# EnergyHarvestingBoard.net
KiCad netlist of a schematic drawn in Altium Designer
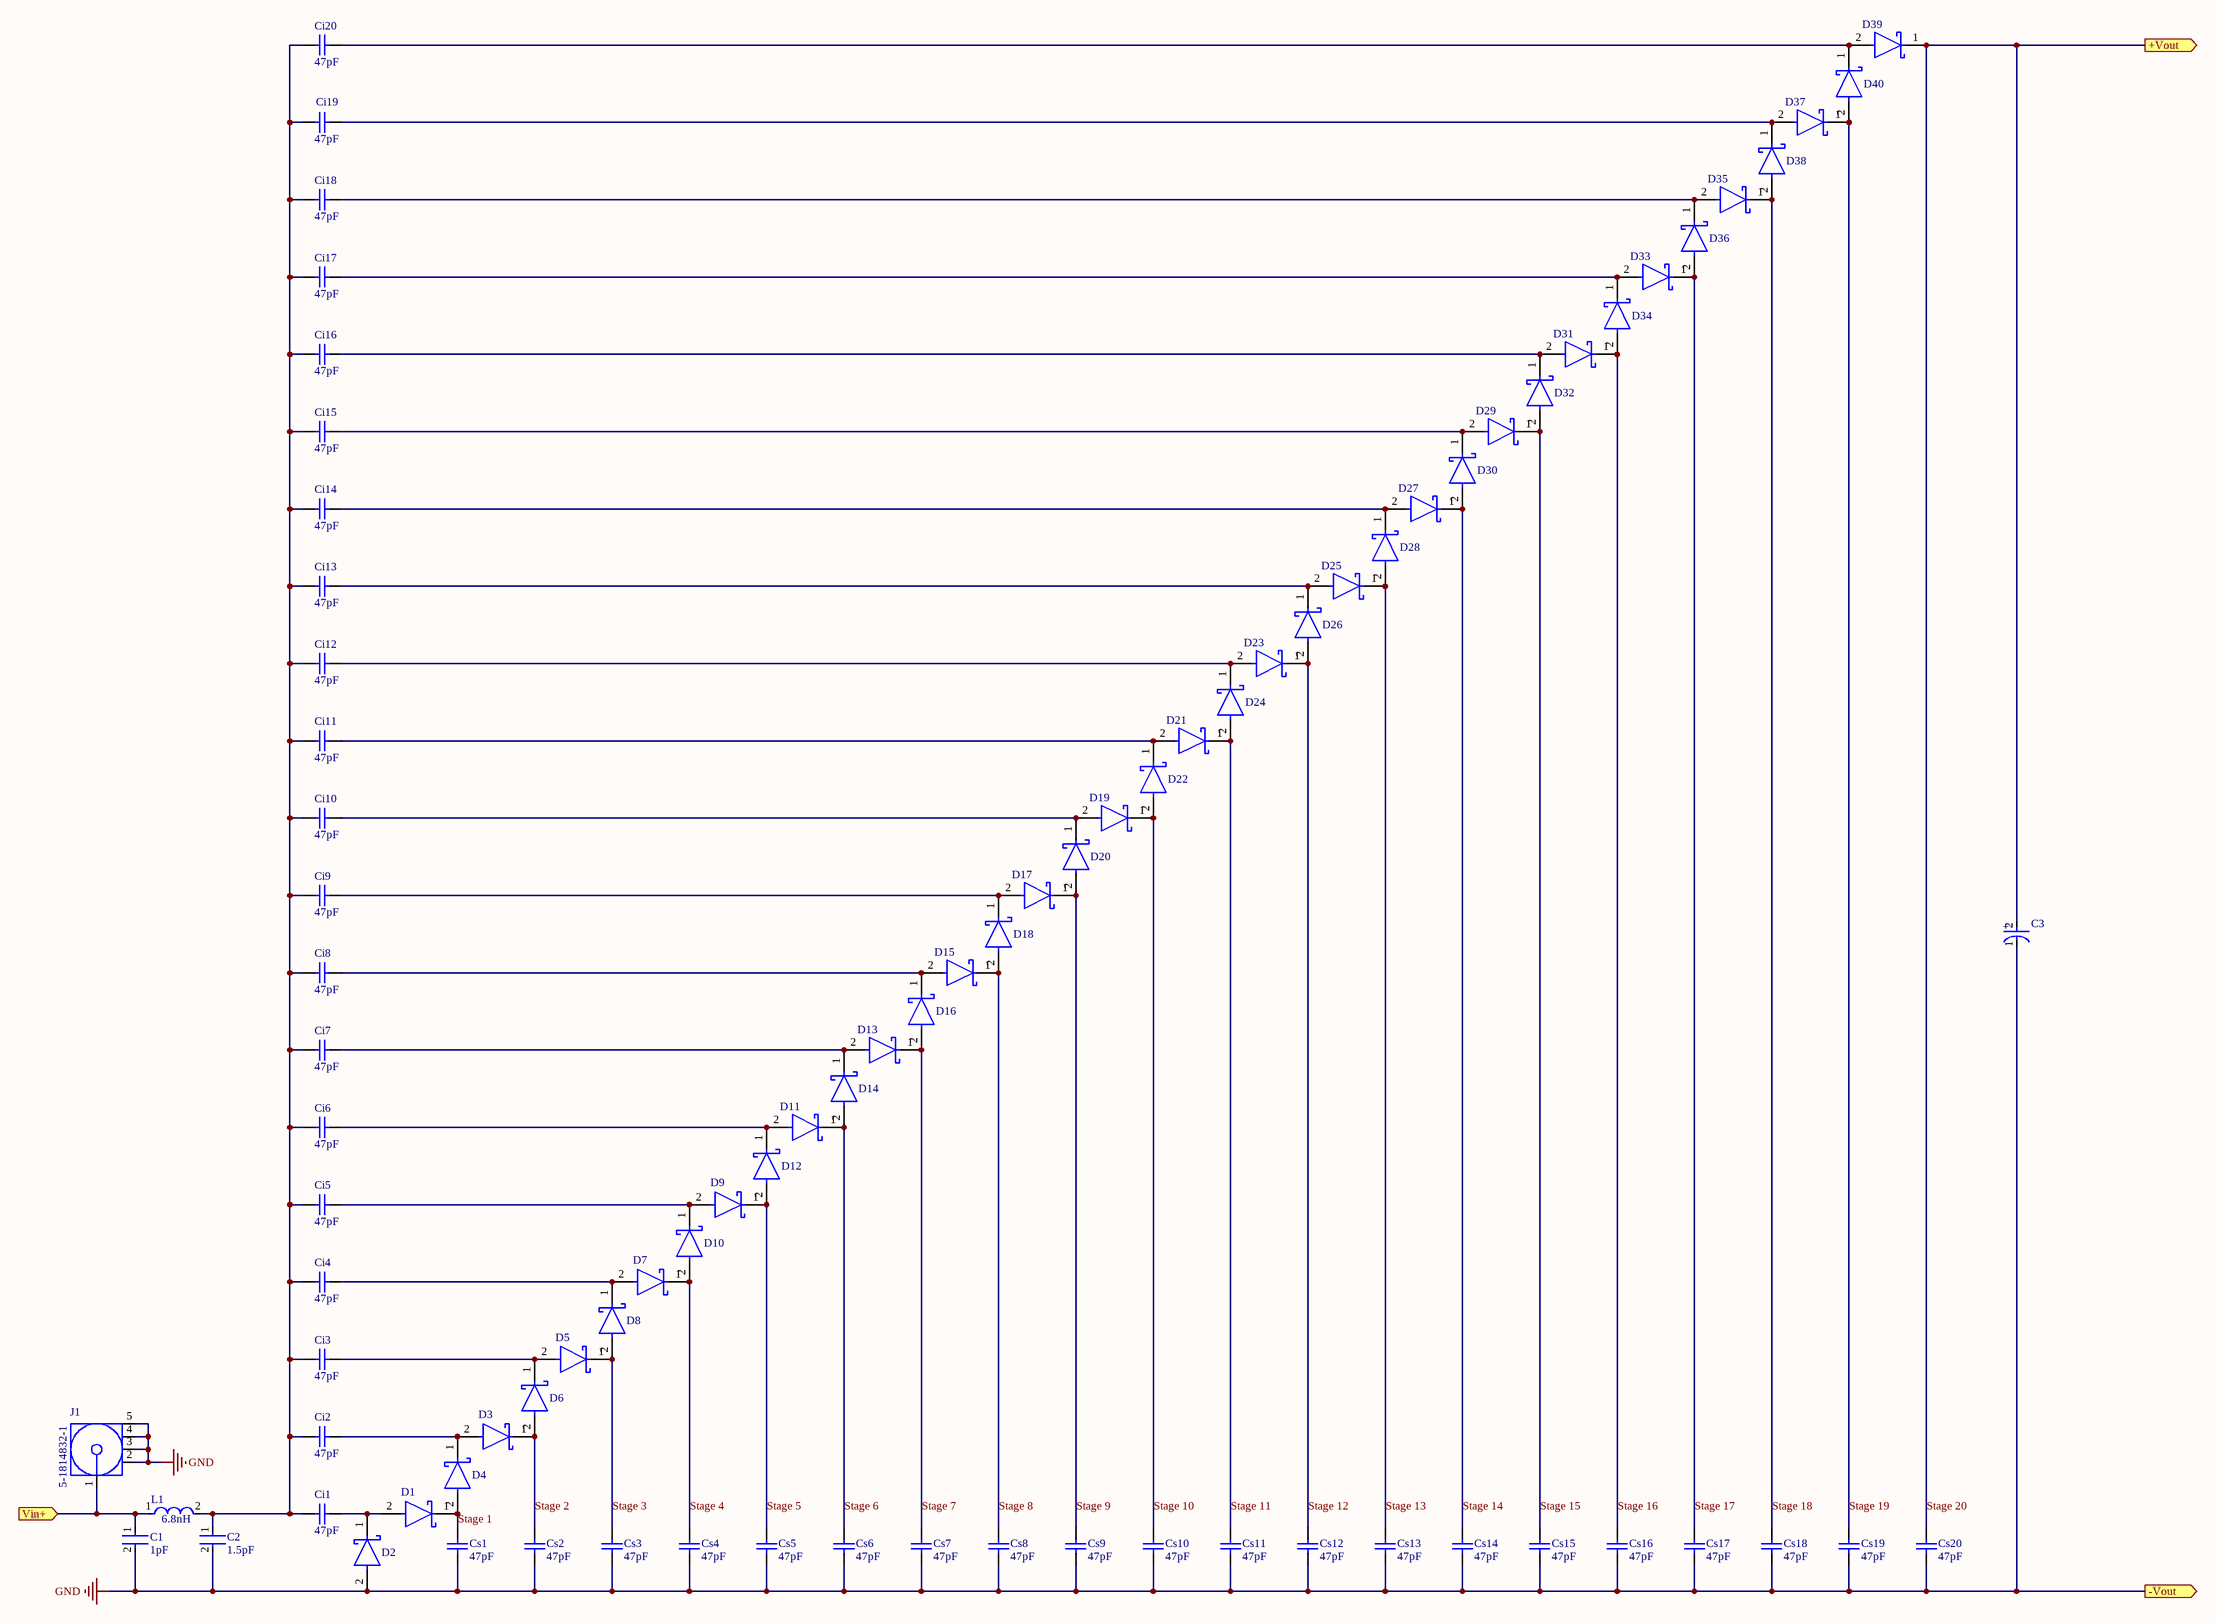
[diagram p0: EnergyHarvestingBoard.SchDoc]

(export (version "E")
  (design (tool "Eeschema 10.0.6"))
  (components
    (comp (ref "C1")
      (value "1pF")
      (footprint "FP-CBR04C-MFG")
      (description "CAP CER 1PF 100V C0G/NP0 0402")
      (fields
        (field (name "MANUFACTURER PART NUMBER") "CBR04C109B1GAC")
        (field (name "MANUFACTURER") "KEMET")
      )
      (libsource (lib "Altium Content Vault") (part "236180d848d6139a670b325ea6854c9"))
    )
    (comp (ref "C2")
      (value "1.5pF")
      (footprint "FP-CBR04C-MFG")
      (description "CBR0402 1.5 pF 30ppm/°C 0.1 pF C0G 100 V")
      (fields (field (name "MANUFACTURER PART NUMBER") "CBR04C159B1GAC"))
      (libsource (lib "Altium Content Vault") (part "236180d848d6139a670b325ea6854c9"))
    )
    (comp (ref "C3")
      (value "EEUEB1JR47S")
      (footprint "FP-RAD-TH-D_5_0_5-L_11_1-MFG")
      (description "Aluminum Electrolytic Capacitors (Radial Lead Type) 0.47uF ±20% 63V")
      (fields (field (name "TOLERANCE") "20%") (field (name "VOLTAGE") "63V"))
      (libsource (lib "Altium Content Vault") (part "a00bbbee19879c290e62620ae7e47b1"))
    )
    (comp (ref "Ci1")
      (value "47pF")
      (footprint "CAPC1005X56X25NL10T15")
      (fields
        (field (name "PART NUMBER") "0402YA470KAT2A")
        (field (name "MANUFACTURER") "AVX Interconnect / Elco")
      )
      (libsource (lib "Altium Content Vault") (part "CAP"))
    )
    (comp (ref "Ci2")
      (value "47pF")
      (footprint "CAPC1005X56X25NL10T15")
      (fields
        (field (name "PART NUMBER") "0402YA470KAT2A")
        (field (name "MANUFACTURER") "AVX Interconnect / Elco")
      )
      (libsource (lib "Altium Content Vault") (part "CAP"))
    )
    (comp (ref "Ci3")
      (value "47pF")
      (footprint "CAPC1005X56X25NL10T15")
      (fields
        (field (name "PART NUMBER") "0402YA470KAT2A")
        (field (name "MANUFACTURER") "AVX Interconnect / Elco")
      )
      (libsource (lib "Altium Content Vault") (part "CAP"))
    )
    (comp (ref "Ci4")
      (value "47pF")
      (footprint "CAPC1005X56X25NL10T15")
      (fields
        (field (name "PART NUMBER") "0402YA470KAT2A")
        (field (name "MANUFACTURER") "AVX Interconnect / Elco")
      )
      (libsource (lib "Altium Content Vault") (part "CAP"))
    )
    (comp (ref "Ci5")
      (value "47pF")
      (footprint "CAPC1005X56X25NL10T15")
      (fields
        (field (name "PART NUMBER") "0402YA470KAT2A")
        (field (name "MANUFACTURER") "AVX Interconnect / Elco")
      )
      (libsource (lib "Altium Content Vault") (part "CAP"))
    )
    (comp (ref "Ci6")
      (value "47pF")
      (footprint "CAPC1005X56X25NL10T15")
      (fields
        (field (name "PART NUMBER") "0402YA470KAT2A")
        (field (name "MANUFACTURER") "AVX Interconnect / Elco")
      )
      (libsource (lib "Altium Content Vault") (part "CAP"))
    )
    (comp (ref "Ci7")
      (value "47pF")
      (footprint "CAPC1005X56X25NL10T15")
      (fields
        (field (name "PART NUMBER") "0402YA470KAT2A")
        (field (name "MANUFACTURER") "AVX Interconnect / Elco")
      )
      (libsource (lib "Altium Content Vault") (part "CAP"))
    )
    (comp (ref "Ci8")
      (value "47pF")
      (footprint "CAPC1005X56X25NL10T15")
      (fields
        (field (name "PART NUMBER") "0402YA470KAT2A")
        (field (name "MANUFACTURER") "AVX Interconnect / Elco")
      )
      (libsource (lib "Altium Content Vault") (part "CAP"))
    )
    (comp (ref "Ci9")
      (value "47pF")
      (footprint "CAPC1005X56X25NL10T15")
      (fields
        (field (name "PART NUMBER") "0402YA470KAT2A")
        (field (name "MANUFACTURER") "AVX Interconnect / Elco")
      )
      (libsource (lib "Altium Content Vault") (part "CAP"))
    )
    (comp (ref "Ci10")
      (value "47pF")
      (footprint "CAPC1005X56X25NL10T15")
      (fields
        (field (name "PART NUMBER") "0402YA470KAT2A")
        (field (name "MANUFACTURER") "AVX Interconnect / Elco")
      )
      (libsource (lib "Altium Content Vault") (part "CAP"))
    )
    (comp (ref "Ci11")
      (value "47pF")
      (footprint "CAPC1005X56X25NL10T15")
      (fields
        (field (name "PART NUMBER") "0402YA470KAT2A")
        (field (name "MANUFACTURER") "AVX Interconnect / Elco")
      )
      (libsource (lib "Altium Content Vault") (part "CAP"))
    )
    (comp (ref "Ci12")
      (value "47pF")
      (footprint "CAPC1005X56X25NL10T15")
      (fields
        (field (name "PART NUMBER") "0402YA470KAT2A")
        (field (name "MANUFACTURER") "AVX Interconnect / Elco")
      )
      (libsource (lib "Altium Content Vault") (part "CAP"))
    )
    (comp (ref "Ci13")
      (value "47pF")
      (footprint "CAPC1005X56X25NL10T15")
      (fields
        (field (name "PART NUMBER") "0402YA470KAT2A")
        (field (name "MANUFACTURER") "AVX Interconnect / Elco")
      )
      (libsource (lib "Altium Content Vault") (part "CAP"))
    )
    (comp (ref "Ci14")
      (value "47pF")
      (footprint "CAPC1005X56X25NL10T15")
      (fields
        (field (name "PART NUMBER") "0402YA470KAT2A")
        (field (name "MANUFACTURER") "AVX Interconnect / Elco")
      )
      (libsource (lib "Altium Content Vault") (part "CAP"))
    )
    (comp (ref "Ci15")
      (value "47pF")
      (footprint "CAPC1005X56X25NL10T15")
      (fields
        (field (name "PART NUMBER") "0402YA470KAT2A")
        (field (name "MANUFACTURER") "AVX Interconnect / Elco")
      )
      (libsource (lib "Altium Content Vault") (part "CAP"))
    )
    (comp (ref "Ci16")
      (value "47pF")
      (footprint "CAPC1005X56X25NL10T15")
      (fields
        (field (name "PART NUMBER") "0402YA470KAT2A")
        (field (name "MANUFACTURER") "AVX Interconnect / Elco")
      )
      (libsource (lib "Altium Content Vault") (part "CAP"))
    )
    (comp (ref "Ci17")
      (value "47pF")
      (footprint "CAPC1005X56X25NL10T15")
      (fields
        (field (name "PART NUMBER") "0402YA470KAT2A")
        (field (name "MANUFACTURER") "AVX Interconnect / Elco")
      )
      (libsource (lib "Altium Content Vault") (part "CAP"))
    )
    (comp (ref "Ci18")
      (value "47pF")
      (footprint "CAPC1005X56X25NL10T15")
      (fields
        (field (name "PART NUMBER") "0402YA470KAT2A")
        (field (name "MANUFACTURER") "AVX Interconnect / Elco")
      )
      (libsource (lib "Altium Content Vault") (part "CAP"))
    )
    (comp (ref "Ci19")
      (value "47pF")
      (footprint "CAPC1005X56X25NL10T15")
      (fields
        (field (name "PART NUMBER") "0402YA470KAT2A")
        (field (name "MANUFACTURER") "AVX Interconnect / Elco")
      )
      (libsource (lib "Altium Content Vault") (part "CAP"))
    )
    (comp (ref "Ci20")
      (value "47pF")
      (footprint "CAPC1005X56X25NL10T15")
      (fields
        (field (name "PART NUMBER") "0402YA470KAT2A")
        (field (name "MANUFACTURER") "AVX Interconnect / Elco")
      )
      (libsource (lib "Altium Content Vault") (part "CAP"))
    )
    (comp (ref "Cs1")
      (value "47pF")
      (footprint "CAPC1005X56X25NL10T15")
      (fields
        (field (name "PART NUMBER") "0402YA470KAT2A")
        (field (name "MANUFACTURER") "AVX Interconnect / Elco")
      )
      (libsource (lib "Altium Content Vault") (part "CAP"))
    )
    (comp (ref "Cs2")
      (value "47pF")
      (footprint "CAPC1005X56X25NL10T15")
      (fields
        (field (name "PART NUMBER") "0402YA470KAT2A")
        (field (name "MANUFACTURER") "AVX Interconnect / Elco")
      )
      (libsource (lib "Altium Content Vault") (part "CAP"))
    )
    (comp (ref "Cs3")
      (value "47pF")
      (footprint "CAPC1005X56X25NL10T15")
      (fields
        (field (name "PART NUMBER") "0402YA470KAT2A")
        (field (name "MANUFACTURER") "AVX Interconnect / Elco")
      )
      (libsource (lib "Altium Content Vault") (part "CAP"))
    )
    (comp (ref "Cs4")
      (value "47pF")
      (footprint "CAPC1005X56X25NL10T15")
      (fields
        (field (name "PART NUMBER") "0402YA470KAT2A")
        (field (name "MANUFACTURER") "AVX Interconnect / Elco")
      )
      (libsource (lib "Altium Content Vault") (part "CAP"))
    )
    (comp (ref "Cs5")
      (value "47pF")
      (footprint "CAPC1005X56X25NL10T15")
      (fields
        (field (name "PART NUMBER") "0402YA470KAT2A")
        (field (name "MANUFACTURER") "AVX Interconnect / Elco")
      )
      (libsource (lib "Altium Content Vault") (part "CAP"))
    )
    (comp (ref "Cs6")
      (value "47pF")
      (footprint "CAPC1005X56X25NL10T15")
      (fields
        (field (name "PART NUMBER") "0402YA470KAT2A")
        (field (name "MANUFACTURER") "AVX Interconnect / Elco")
      )
      (libsource (lib "Altium Content Vault") (part "CAP"))
    )
    (comp (ref "Cs7")
      (value "47pF")
      (footprint "CAPC1005X56X25NL10T15")
      (fields
        (field (name "PART NUMBER") "0402YA470KAT2A")
        (field (name "MANUFACTURER") "AVX Interconnect / Elco")
      )
      (libsource (lib "Altium Content Vault") (part "CAP"))
    )
    (comp (ref "Cs8")
      (value "47pF")
      (footprint "CAPC1005X56X25NL10T15")
      (fields
        (field (name "PART NUMBER") "0402YA470KAT2A")
        (field (name "MANUFACTURER") "AVX Interconnect / Elco")
      )
      (libsource (lib "Altium Content Vault") (part "CAP"))
    )
    (comp (ref "Cs9")
      (value "47pF")
      (footprint "CAPC1005X56X25NL10T15")
      (fields
        (field (name "PART NUMBER") "0402YA470KAT2A")
        (field (name "MANUFACTURER") "AVX Interconnect / Elco")
      )
      (libsource (lib "Altium Content Vault") (part "CAP"))
    )
    (comp (ref "Cs10")
      (value "47pF")
      (footprint "CAPC1005X56X25NL10T15")
      (fields
        (field (name "PART NUMBER") "0402YA470KAT2A")
        (field (name "MANUFACTURER") "AVX Interconnect / Elco")
      )
      (libsource (lib "Altium Content Vault") (part "CAP"))
    )
    (comp (ref "Cs11")
      (value "47pF")
      (footprint "CAPC1005X56X25NL10T15")
      (fields
        (field (name "PART NUMBER") "0402YA470KAT2A")
        (field (name "MANUFACTURER") "AVX Interconnect / Elco")
      )
      (libsource (lib "Altium Content Vault") (part "CAP"))
    )
    (comp (ref "Cs12")
      (value "47pF")
      (footprint "CAPC1005X56X25NL10T15")
      (fields
        (field (name "PART NUMBER") "0402YA470KAT2A")
        (field (name "MANUFACTURER") "AVX Interconnect / Elco")
      )
      (libsource (lib "Altium Content Vault") (part "CAP"))
    )
    (comp (ref "Cs13")
      (value "47pF")
      (footprint "CAPC1005X56X25NL10T15")
      (fields
        (field (name "PART NUMBER") "0402YA470KAT2A")
        (field (name "MANUFACTURER") "AVX Interconnect / Elco")
      )
      (libsource (lib "Altium Content Vault") (part "CAP"))
    )
    (comp (ref "Cs14")
      (value "47pF")
      (footprint "CAPC1005X56X25NL10T15")
      (fields
        (field (name "PART NUMBER") "0402YA470KAT2A")
        (field (name "MANUFACTURER") "AVX Interconnect / Elco")
      )
      (libsource (lib "Altium Content Vault") (part "CAP"))
    )
    (comp (ref "Cs15")
      (value "47pF")
      (footprint "CAPC1005X56X25NL10T15")
      (fields
        (field (name "PART NUMBER") "0402YA470KAT2A")
        (field (name "MANUFACTURER") "AVX Interconnect / Elco")
      )
      (libsource (lib "Altium Content Vault") (part "CAP"))
    )
    (comp (ref "Cs16")
      (value "47pF")
      (footprint "CAPC1005X56X25NL10T15")
      (fields
        (field (name "PART NUMBER") "0402YA470KAT2A")
        (field (name "MANUFACTURER") "AVX Interconnect / Elco")
      )
      (libsource (lib "Altium Content Vault") (part "CAP"))
    )
    (comp (ref "Cs17")
      (value "47pF")
      (footprint "CAPC1005X56X25NL10T15")
      (fields
        (field (name "PART NUMBER") "0402YA470KAT2A")
        (field (name "MANUFACTURER") "AVX Interconnect / Elco")
      )
      (libsource (lib "Altium Content Vault") (part "CAP"))
    )
    (comp (ref "Cs18")
      (value "47pF")
      (footprint "CAPC1005X56X25NL10T15")
      (fields
        (field (name "PART NUMBER") "0402YA470KAT2A")
        (field (name "MANUFACTURER") "AVX Interconnect / Elco")
      )
      (libsource (lib "Altium Content Vault") (part "CAP"))
    )
    (comp (ref "Cs19")
      (value "47pF")
      (footprint "CAPC1005X56X25NL10T15")
      (fields
        (field (name "PART NUMBER") "0402YA470KAT2A")
        (field (name "MANUFACTURER") "AVX Interconnect / Elco")
      )
      (libsource (lib "Altium Content Vault") (part "CAP"))
    )
    (comp (ref "Cs20")
      (value "47pF")
      (footprint "CAPC1005X56X25NL10T15")
      (fields
        (field (name "PART NUMBER") "0402YA470KAT2A")
        (field (name "MANUFACTURER") "AVX Interconnect / Elco")
      )
      (libsource (lib "Altium Content Vault") (part "CAP"))
    )
    (comp (ref "D1")
      (value "CDBQR0130L")
      (footprint "FP-0402-SOD-923F-MFG")
      (description "DIODE SCHOTTKY 30V 100MA 0402")
      (libsource (lib "Altium Content Vault") (part "1d6ec82d83fb6aee721767c19dac4b9"))
    )
    (comp (ref "D2")
      (value "CDBQR0130L")
      (footprint "FP-0402-SOD-923F-MFG")
      (description "DIODE SCHOTTKY 30V 100MA 0402")
      (libsource (lib "Altium Content Vault") (part "1d6ec82d83fb6aee721767c19dac4b9"))
    )
    (comp (ref "D3")
      (value "CDBQR0130L")
      (footprint "FP-0402-SOD-923F-MFG")
      (description "DIODE SCHOTTKY 30V 100MA 0402")
      (libsource (lib "Altium Content Vault") (part "1d6ec82d83fb6aee721767c19dac4b9"))
    )
    (comp (ref "D4")
      (value "CDBQR0130L")
      (footprint "FP-0402-SOD-923F-MFG")
      (description "DIODE SCHOTTKY 30V 100MA 0402")
      (libsource (lib "Altium Content Vault") (part "1d6ec82d83fb6aee721767c19dac4b9"))
    )
    (comp (ref "D5")
      (value "CDBQR0130L")
      (footprint "FP-0402-SOD-923F-MFG")
      (description "DIODE SCHOTTKY 30V 100MA 0402")
      (libsource (lib "Altium Content Vault") (part "1d6ec82d83fb6aee721767c19dac4b9"))
    )
    (comp (ref "D6")
      (value "CDBQR0130L")
      (footprint "FP-0402-SOD-923F-MFG")
      (description "DIODE SCHOTTKY 30V 100MA 0402")
      (libsource (lib "Altium Content Vault") (part "1d6ec82d83fb6aee721767c19dac4b9"))
    )
    (comp (ref "D7")
      (value "CDBQR0130L")
      (footprint "FP-0402-SOD-923F-MFG")
      (description "DIODE SCHOTTKY 30V 100MA 0402")
      (libsource (lib "Altium Content Vault") (part "1d6ec82d83fb6aee721767c19dac4b9"))
    )
    (comp (ref "D8")
      (value "CDBQR0130L")
      (footprint "FP-0402-SOD-923F-MFG")
      (description "DIODE SCHOTTKY 30V 100MA 0402")
      (libsource (lib "Altium Content Vault") (part "1d6ec82d83fb6aee721767c19dac4b9"))
    )
    (comp (ref "D9")
      (value "CDBQR0130L")
      (footprint "FP-0402-SOD-923F-MFG")
      (description "DIODE SCHOTTKY 30V 100MA 0402")
      (libsource (lib "Altium Content Vault") (part "1d6ec82d83fb6aee721767c19dac4b9"))
    )
    (comp (ref "D10")
      (value "CDBQR0130L")
      (footprint "FP-0402-SOD-923F-MFG")
      (description "DIODE SCHOTTKY 30V 100MA 0402")
      (libsource (lib "Altium Content Vault") (part "1d6ec82d83fb6aee721767c19dac4b9"))
    )
    (comp (ref "D11")
      (value "CDBQR0130L")
      (footprint "FP-0402-SOD-923F-MFG")
      (description "DIODE SCHOTTKY 30V 100MA 0402")
      (libsource (lib "Altium Content Vault") (part "1d6ec82d83fb6aee721767c19dac4b9"))
    )
    (comp (ref "D12")
      (value "CDBQR0130L")
      (footprint "FP-0402-SOD-923F-MFG")
      (description "DIODE SCHOTTKY 30V 100MA 0402")
      (libsource (lib "Altium Content Vault") (part "1d6ec82d83fb6aee721767c19dac4b9"))
    )
    (comp (ref "D13")
      (value "CDBQR0130L")
      (footprint "FP-0402-SOD-923F-MFG")
      (description "DIODE SCHOTTKY 30V 100MA 0402")
      (libsource (lib "Altium Content Vault") (part "1d6ec82d83fb6aee721767c19dac4b9"))
    )
    (comp (ref "D14")
      (value "CDBQR0130L")
      (footprint "FP-0402-SOD-923F-MFG")
      (description "DIODE SCHOTTKY 30V 100MA 0402")
      (libsource (lib "Altium Content Vault") (part "1d6ec82d83fb6aee721767c19dac4b9"))
    )
    (comp (ref "D15")
      (value "CDBQR0130L")
      (footprint "FP-0402-SOD-923F-MFG")
      (description "DIODE SCHOTTKY 30V 100MA 0402")
      (libsource (lib "Altium Content Vault") (part "1d6ec82d83fb6aee721767c19dac4b9"))
    )
    (comp (ref "D16")
      (value "CDBQR0130L")
      (footprint "FP-0402-SOD-923F-MFG")
      (description "DIODE SCHOTTKY 30V 100MA 0402")
      (libsource (lib "Altium Content Vault") (part "1d6ec82d83fb6aee721767c19dac4b9"))
    )
    (comp (ref "D17")
      (value "CDBQR0130L")
      (footprint "FP-0402-SOD-923F-MFG")
      (description "DIODE SCHOTTKY 30V 100MA 0402")
      (libsource (lib "Altium Content Vault") (part "1d6ec82d83fb6aee721767c19dac4b9"))
    )
    (comp (ref "D18")
      (value "CDBQR0130L")
      (footprint "FP-0402-SOD-923F-MFG")
      (description "DIODE SCHOTTKY 30V 100MA 0402")
      (libsource (lib "Altium Content Vault") (part "1d6ec82d83fb6aee721767c19dac4b9"))
    )
    (comp (ref "D19")
      (value "CDBQR0130L")
      (footprint "FP-0402-SOD-923F-MFG")
      (description "DIODE SCHOTTKY 30V 100MA 0402")
      (libsource (lib "Altium Content Vault") (part "1d6ec82d83fb6aee721767c19dac4b9"))
    )
    (comp (ref "D20")
      (value "CDBQR0130L")
      (footprint "FP-0402-SOD-923F-MFG")
      (description "DIODE SCHOTTKY 30V 100MA 0402")
      (libsource (lib "Altium Content Vault") (part "1d6ec82d83fb6aee721767c19dac4b9"))
    )
    (comp (ref "D21")
      (value "CDBQR0130L")
      (footprint "FP-0402-SOD-923F-MFG")
      (description "DIODE SCHOTTKY 30V 100MA 0402")
      (libsource (lib "Altium Content Vault") (part "1d6ec82d83fb6aee721767c19dac4b9"))
    )
    (comp (ref "D22")
      (value "CDBQR0130L")
      (footprint "FP-0402-SOD-923F-MFG")
      (description "DIODE SCHOTTKY 30V 100MA 0402")
      (libsource (lib "Altium Content Vault") (part "1d6ec82d83fb6aee721767c19dac4b9"))
    )
    (comp (ref "D23")
      (value "CDBQR0130L")
      (footprint "FP-0402-SOD-923F-MFG")
      (description "DIODE SCHOTTKY 30V 100MA 0402")
      (libsource (lib "Altium Content Vault") (part "1d6ec82d83fb6aee721767c19dac4b9"))
    )
    (comp (ref "D24")
      (value "CDBQR0130L")
      (footprint "FP-0402-SOD-923F-MFG")
      (description "DIODE SCHOTTKY 30V 100MA 0402")
      (libsource (lib "Altium Content Vault") (part "1d6ec82d83fb6aee721767c19dac4b9"))
    )
    (comp (ref "D25")
      (value "CDBQR0130L")
      (footprint "FP-0402-SOD-923F-MFG")
      (description "DIODE SCHOTTKY 30V 100MA 0402")
      (libsource (lib "Altium Content Vault") (part "1d6ec82d83fb6aee721767c19dac4b9"))
    )
    (comp (ref "D26")
      (value "CDBQR0130L")
      (footprint "FP-0402-SOD-923F-MFG")
      (description "DIODE SCHOTTKY 30V 100MA 0402")
      (libsource (lib "Altium Content Vault") (part "1d6ec82d83fb6aee721767c19dac4b9"))
    )
    (comp (ref "D27")
      (value "CDBQR0130L")
      (footprint "FP-0402-SOD-923F-MFG")
      (description "DIODE SCHOTTKY 30V 100MA 0402")
      (libsource (lib "Altium Content Vault") (part "1d6ec82d83fb6aee721767c19dac4b9"))
    )
    (comp (ref "D28")
      (value "CDBQR0130L")
      (footprint "FP-0402-SOD-923F-MFG")
      (description "DIODE SCHOTTKY 30V 100MA 0402")
      (libsource (lib "Altium Content Vault") (part "1d6ec82d83fb6aee721767c19dac4b9"))
    )
    (comp (ref "D29")
      (value "CDBQR0130L")
      (footprint "FP-0402-SOD-923F-MFG")
      (description "DIODE SCHOTTKY 30V 100MA 0402")
      (libsource (lib "Altium Content Vault") (part "1d6ec82d83fb6aee721767c19dac4b9"))
    )
    (comp (ref "D30")
      (value "CDBQR0130L")
      (footprint "FP-0402-SOD-923F-MFG")
      (description "DIODE SCHOTTKY 30V 100MA 0402")
      (libsource (lib "Altium Content Vault") (part "1d6ec82d83fb6aee721767c19dac4b9"))
    )
    (comp (ref "D31")
      (value "CDBQR0130L")
      (footprint "FP-0402-SOD-923F-MFG")
      (description "DIODE SCHOTTKY 30V 100MA 0402")
      (libsource (lib "Altium Content Vault") (part "1d6ec82d83fb6aee721767c19dac4b9"))
    )
    (comp (ref "D32")
      (value "CDBQR0130L")
      (footprint "FP-0402-SOD-923F-MFG")
      (description "DIODE SCHOTTKY 30V 100MA 0402")
      (libsource (lib "Altium Content Vault") (part "1d6ec82d83fb6aee721767c19dac4b9"))
    )
    (comp (ref "D33")
      (value "CDBQR0130L")
      (footprint "FP-0402-SOD-923F-MFG")
      (description "DIODE SCHOTTKY 30V 100MA 0402")
      (libsource (lib "Altium Content Vault") (part "1d6ec82d83fb6aee721767c19dac4b9"))
    )
    (comp (ref "D34")
      (value "CDBQR0130L")
      (footprint "FP-0402-SOD-923F-MFG")
      (description "DIODE SCHOTTKY 30V 100MA 0402")
      (libsource (lib "Altium Content Vault") (part "1d6ec82d83fb6aee721767c19dac4b9"))
    )
    (comp (ref "D35")
      (value "CDBQR0130L")
      (footprint "FP-0402-SOD-923F-MFG")
      (description "DIODE SCHOTTKY 30V 100MA 0402")
      (libsource (lib "Altium Content Vault") (part "1d6ec82d83fb6aee721767c19dac4b9"))
    )
    (comp (ref "D36")
      (value "CDBQR0130L")
      (footprint "FP-0402-SOD-923F-MFG")
      (description "DIODE SCHOTTKY 30V 100MA 0402")
      (libsource (lib "Altium Content Vault") (part "1d6ec82d83fb6aee721767c19dac4b9"))
    )
    (comp (ref "D37")
      (value "CDBQR0130L")
      (footprint "FP-0402-SOD-923F-MFG")
      (description "DIODE SCHOTTKY 30V 100MA 0402")
      (libsource (lib "Altium Content Vault") (part "1d6ec82d83fb6aee721767c19dac4b9"))
    )
    (comp (ref "D38")
      (value "CDBQR0130L")
      (footprint "FP-0402-SOD-923F-MFG")
      (description "DIODE SCHOTTKY 30V 100MA 0402")
      (libsource (lib "Altium Content Vault") (part "1d6ec82d83fb6aee721767c19dac4b9"))
    )
    (comp (ref "D39")
      (value "CDBQR0130L")
      (footprint "FP-0402-SOD-923F-MFG")
      (description "DIODE SCHOTTKY 30V 100MA 0402")
      (libsource (lib "Altium Content Vault") (part "1d6ec82d83fb6aee721767c19dac4b9"))
    )
    (comp (ref "D40")
      (value "CDBQR0130L")
      (footprint "FP-0402-SOD-923F-MFG")
      (description "DIODE SCHOTTKY 30V 100MA 0402")
      (libsource (lib "Altium Content Vault") (part "1d6ec82d83fb6aee721767c19dac4b9"))
    )
    (comp (ref "J1")
      (value "5-1814832-1")
      (footprint "TECO-5-1814832-1_V")
      (fields (field (name "MANUFACTURER") "TE Connectivity"))
      (libsource (lib "Altium Content Vault") (part "CN-S-4F-RF5"))
    )
    (comp (ref "L1")
      (value "6.8nH")
      (footprint "FP-LQW18AN_00-MFG")
      (description "Wire Wound RF Inductor 6.8nH ±0.5nH 750mA 0.082Ω 0603 (1608)")
      (libsource (lib "Altium Content Vault") (part "725321dda6339637d4d059423bc1c3c"))
    )
  )
  (nets
    (net (code "1") (name "/Stage 1") (class "Default")
      (node (ref "Cs1") (pin "1") (pinfunction "1_1") (pintype "passive"))
      (node (ref "D1") (pin "1") (pinfunction "C_1") (pintype "passive"))
      (node (ref "D4") (pin "2") (pinfunction "A_2") (pintype "passive"))
    )
    (net (code "2") (name "/Stage 2") (class "Default")
      (node (ref "Cs2") (pin "1") (pinfunction "1_1") (pintype "passive"))
      (node (ref "D3") (pin "1") (pinfunction "C_1") (pintype "passive"))
      (node (ref "D6") (pin "2") (pinfunction "A_2") (pintype "passive"))
    )
    (net (code "3") (name "/Stage 3") (class "Default")
      (node (ref "Cs3") (pin "1") (pinfunction "1_1") (pintype "passive"))
      (node (ref "D5") (pin "1") (pinfunction "C_1") (pintype "passive"))
      (node (ref "D8") (pin "2") (pinfunction "A_2") (pintype "passive"))
    )
    (net (code "4") (name "/Stage 4") (class "Default")
      (node (ref "Cs4") (pin "1") (pinfunction "1_1") (pintype "passive"))
      (node (ref "D10") (pin "2") (pinfunction "A_2") (pintype "passive"))
      (node (ref "D7") (pin "1") (pinfunction "C_1") (pintype "passive"))
    )
    (net (code "5") (name "/Stage 5") (class "Default")
      (node (ref "Cs5") (pin "1") (pinfunction "1_1") (pintype "passive"))
      (node (ref "D12") (pin "2") (pinfunction "A_2") (pintype "passive"))
      (node (ref "D9") (pin "1") (pinfunction "C_1") (pintype "passive"))
    )
    (net (code "6") (name "/Stage 6") (class "Default")
      (node (ref "Cs6") (pin "1") (pinfunction "1_1") (pintype "passive"))
      (node (ref "D11") (pin "1") (pinfunction "C_1") (pintype "passive"))
      (node (ref "D14") (pin "2") (pinfunction "A_2") (pintype "passive"))
    )
    (net (code "7") (name "/Stage 7") (class "Default")
      (node (ref "Cs7") (pin "1") (pinfunction "1_1") (pintype "passive"))
      (node (ref "D13") (pin "1") (pinfunction "C_1") (pintype "passive"))
      (node (ref "D16") (pin "2") (pinfunction "A_2") (pintype "passive"))
    )
    (net (code "8") (name "/Stage 8") (class "Default")
      (node (ref "Cs8") (pin "1") (pinfunction "1_1") (pintype "passive"))
      (node (ref "D15") (pin "1") (pinfunction "C_1") (pintype "passive"))
      (node (ref "D18") (pin "2") (pinfunction "A_2") (pintype "passive"))
    )
    (net (code "9") (name "/Stage 9") (class "Default")
      (node (ref "Cs9") (pin "1") (pinfunction "1_1") (pintype "passive"))
      (node (ref "D17") (pin "1") (pinfunction "C_1") (pintype "passive"))
      (node (ref "D20") (pin "2") (pinfunction "A_2") (pintype "passive"))
    )
    (net (code "10") (name "/Stage 10") (class "Default")
      (node (ref "Cs10") (pin "1") (pinfunction "1_1") (pintype "passive"))
      (node (ref "D19") (pin "1") (pinfunction "C_1") (pintype "passive"))
      (node (ref "D22") (pin "2") (pinfunction "A_2") (pintype "passive"))
    )
    (net (code "11") (name "/Stage 11") (class "Default")
      (node (ref "Cs11") (pin "1") (pinfunction "1_1") (pintype "passive"))
      (node (ref "D21") (pin "1") (pinfunction "C_1") (pintype "passive"))
      (node (ref "D24") (pin "2") (pinfunction "A_2") (pintype "passive"))
    )
    (net (code "12") (name "/Stage 12") (class "Default")
      (node (ref "Cs12") (pin "1") (pinfunction "1_1") (pintype "passive"))
      (node (ref "D23") (pin "1") (pinfunction "C_1") (pintype "passive"))
      (node (ref "D26") (pin "2") (pinfunction "A_2") (pintype "passive"))
    )
    (net (code "13") (name "/Stage 13") (class "Default")
      (node (ref "Cs13") (pin "1") (pinfunction "1_1") (pintype "passive"))
      (node (ref "D25") (pin "1") (pinfunction "C_1") (pintype "passive"))
      (node (ref "D28") (pin "2") (pinfunction "A_2") (pintype "passive"))
    )
    (net (code "14") (name "/Stage 14") (class "Default")
      (node (ref "Cs14") (pin "1") (pinfunction "1_1") (pintype "passive"))
      (node (ref "D27") (pin "1") (pinfunction "C_1") (pintype "passive"))
      (node (ref "D30") (pin "2") (pinfunction "A_2") (pintype "passive"))
    )
    (net (code "15") (name "/Stage 15") (class "Default")
      (node (ref "Cs15") (pin "1") (pinfunction "1_1") (pintype "passive"))
      (node (ref "D29") (pin "1") (pinfunction "C_1") (pintype "passive"))
      (node (ref "D32") (pin "2") (pinfunction "A_2") (pintype "passive"))
    )
    (net (code "16") (name "/Stage 16") (class "Default")
      (node (ref "Cs16") (pin "1") (pinfunction "1_1") (pintype "passive"))
      (node (ref "D31") (pin "1") (pinfunction "C_1") (pintype "passive"))
      (node (ref "D34") (pin "2") (pinfunction "A_2") (pintype "passive"))
    )
    (net (code "17") (name "/Stage 17") (class "Default")
      (node (ref "Cs17") (pin "1") (pinfunction "1_1") (pintype "passive"))
      (node (ref "D33") (pin "1") (pinfunction "C_1") (pintype "passive"))
      (node (ref "D36") (pin "2") (pinfunction "A_2") (pintype "passive"))
    )
    (net (code "18") (name "/Stage 18") (class "Default")
      (node (ref "Cs18") (pin "1") (pinfunction "1_1") (pintype "passive"))
      (node (ref "D35") (pin "1") (pinfunction "C_1") (pintype "passive"))
      (node (ref "D38") (pin "2") (pinfunction "A_2") (pintype "passive"))
    )
    (net (code "19") (name "/Stage 19") (class "Default")
      (node (ref "Cs19") (pin "1") (pinfunction "1_1") (pintype "passive"))
      (node (ref "D37") (pin "1") (pinfunction "C_1") (pintype "passive"))
      (node (ref "D40") (pin "2") (pinfunction "A_2") (pintype "passive"))
    )
    (net (code "20") (name "/Stage 20") (class "Default")
      (node (ref "C3") (pin "2") (pinfunction "A_2") (pintype "passive"))
      (node (ref "Cs20") (pin "1") (pinfunction "1_1") (pintype "passive"))
      (node (ref "D39") (pin "1") (pinfunction "C_1") (pintype "passive"))
    )
    (net (code "21") (name "/Vin+") (class "Default")
      (node (ref "C1") (pin "1") (pinfunction "1_1") (pintype "passive"))
      (node (ref "J1") (pin "1") (pinfunction "1_1") (pintype "passive"))
      (node (ref "L1") (pin "1") (pinfunction "1_1") (pintype "passive"))
    )
    (net (code "22") (name "GND") (class "Default")
      (node (ref "C1") (pin "2") (pinfunction "2_2") (pintype "passive"))
      (node (ref "C2") (pin "2") (pinfunction "2_2") (pintype "passive"))
      (node (ref "C3") (pin "1") (pinfunction "C_1") (pintype "passive"))
      (node (ref "Cs1") (pin "2") (pinfunction "2_2") (pintype "passive"))
      (node (ref "Cs10") (pin "2") (pinfunction "2_2") (pintype "passive"))
      (node (ref "Cs11") (pin "2") (pinfunction "2_2") (pintype "passive"))
      (node (ref "Cs12") (pin "2") (pinfunction "2_2") (pintype "passive"))
      (node (ref "Cs13") (pin "2") (pinfunction "2_2") (pintype "passive"))
      (node (ref "Cs14") (pin "2") (pinfunction "2_2") (pintype "passive"))
      (node (ref "Cs15") (pin "2") (pinfunction "2_2") (pintype "passive"))
      (node (ref "Cs16") (pin "2") (pinfunction "2_2") (pintype "passive"))
      (node (ref "Cs17") (pin "2") (pinfunction "2_2") (pintype "passive"))
      (node (ref "Cs18") (pin "2") (pinfunction "2_2") (pintype "passive"))
      (node (ref "Cs19") (pin "2") (pinfunction "2_2") (pintype "passive"))
      (node (ref "Cs2") (pin "2") (pinfunction "2_2") (pintype "passive"))
      (node (ref "Cs20") (pin "2") (pinfunction "2_2") (pintype "passive"))
      (node (ref "Cs3") (pin "2") (pinfunction "2_2") (pintype "passive"))
      (node (ref "Cs4") (pin "2") (pinfunction "2_2") (pintype "passive"))
      (node (ref "Cs5") (pin "2") (pinfunction "2_2") (pintype "passive"))
      (node (ref "Cs6") (pin "2") (pinfunction "2_2") (pintype "passive"))
      (node (ref "Cs7") (pin "2") (pinfunction "2_2") (pintype "passive"))
      (node (ref "Cs8") (pin "2") (pinfunction "2_2") (pintype "passive"))
      (node (ref "Cs9") (pin "2") (pinfunction "2_2") (pintype "passive"))
      (node (ref "D2") (pin "2") (pinfunction "A_2") (pintype "passive"))
      (node (ref "J1") (pin "2") (pinfunction "2_2") (pintype "passive"))
      (node (ref "J1") (pin "3") (pinfunction "3_3") (pintype "passive"))
      (node (ref "J1") (pin "4") (pinfunction "4_4") (pintype "passive"))
      (node (ref "J1") (pin "5") (pinfunction "5_5") (pintype "passive"))
    )
    (net (code "23") (name "Net-(C2-Pad1)") (class "Default")
      (node (ref "C2") (pin "1") (pinfunction "1_1") (pintype "passive"))
      (node (ref "Ci1") (pin "1") (pinfunction "1_1") (pintype "passive"))
      (node (ref "Ci10") (pin "1") (pinfunction "1_1") (pintype "passive"))
      (node (ref "Ci11") (pin "1") (pinfunction "1_1") (pintype "passive"))
      (node (ref "Ci12") (pin "1") (pinfunction "1_1") (pintype "passive"))
      (node (ref "Ci13") (pin "1") (pinfunction "1_1") (pintype "passive"))
      (node (ref "Ci14") (pin "1") (pinfunction "1_1") (pintype "passive"))
      (node (ref "Ci15") (pin "1") (pinfunction "1_1") (pintype "passive"))
      (node (ref "Ci16") (pin "1") (pinfunction "1_1") (pintype "passive"))
      (node (ref "Ci17") (pin "1") (pinfunction "1_1") (pintype "passive"))
      (node (ref "Ci18") (pin "1") (pinfunction "1_1") (pintype "passive"))
      (node (ref "Ci19") (pin "1") (pinfunction "1_1") (pintype "passive"))
      (node (ref "Ci2") (pin "1") (pinfunction "1_1") (pintype "passive"))
      (node (ref "Ci20") (pin "1") (pinfunction "1_1") (pintype "passive"))
      (node (ref "Ci3") (pin "1") (pinfunction "1_1") (pintype "passive"))
      (node (ref "Ci4") (pin "1") (pinfunction "1_1") (pintype "passive"))
      (node (ref "Ci5") (pin "1") (pinfunction "1_1") (pintype "passive"))
      (node (ref "Ci6") (pin "1") (pinfunction "1_1") (pintype "passive"))
      (node (ref "Ci7") (pin "1") (pinfunction "1_1") (pintype "passive"))
      (node (ref "Ci8") (pin "1") (pinfunction "1_1") (pintype "passive"))
      (node (ref "Ci9") (pin "1") (pinfunction "1_1") (pintype "passive"))
      (node (ref "L1") (pin "2") (pinfunction "2_2") (pintype "passive"))
    )
    (net (code "24") (name "Net-(D1-A)") (class "Default")
      (node (ref "Ci1") (pin "2") (pinfunction "2_2") (pintype "passive"))
      (node (ref "D1") (pin "2") (pinfunction "A_2") (pintype "passive"))
      (node (ref "D2") (pin "1") (pinfunction "C_1") (pintype "passive"))
    )
    (net (code "25") (name "Net-(D3-A)") (class "Default")
      (node (ref "Ci2") (pin "2") (pinfunction "2_2") (pintype "passive"))
      (node (ref "D3") (pin "2") (pinfunction "A_2") (pintype "passive"))
      (node (ref "D4") (pin "1") (pinfunction "C_1") (pintype "passive"))
    )
    (net (code "26") (name "Net-(D5-A)") (class "Default")
      (node (ref "Ci3") (pin "2") (pinfunction "2_2") (pintype "passive"))
      (node (ref "D5") (pin "2") (pinfunction "A_2") (pintype "passive"))
      (node (ref "D6") (pin "1") (pinfunction "C_1") (pintype "passive"))
    )
    (net (code "27") (name "Net-(D7-A)") (class "Default")
      (node (ref "Ci4") (pin "2") (pinfunction "2_2") (pintype "passive"))
      (node (ref "D7") (pin "2") (pinfunction "A_2") (pintype "passive"))
      (node (ref "D8") (pin "1") (pinfunction "C_1") (pintype "passive"))
    )
    (net (code "28") (name "Net-(D10-C)") (class "Default")
      (node (ref "Ci5") (pin "2") (pinfunction "2_2") (pintype "passive"))
      (node (ref "D10") (pin "1") (pinfunction "C_1") (pintype "passive"))
      (node (ref "D9") (pin "2") (pinfunction "A_2") (pintype "passive"))
    )
    (net (code "29") (name "Net-(D11-A)") (class "Default")
      (node (ref "Ci6") (pin "2") (pinfunction "2_2") (pintype "passive"))
      (node (ref "D11") (pin "2") (pinfunction "A_2") (pintype "passive"))
      (node (ref "D12") (pin "1") (pinfunction "C_1") (pintype "passive"))
    )
    (net (code "30") (name "Net-(D13-A)") (class "Default")
      (node (ref "Ci7") (pin "2") (pinfunction "2_2") (pintype "passive"))
      (node (ref "D13") (pin "2") (pinfunction "A_2") (pintype "passive"))
      (node (ref "D14") (pin "1") (pinfunction "C_1") (pintype "passive"))
    )
    (net (code "31") (name "Net-(D15-A)") (class "Default")
      (node (ref "Ci8") (pin "2") (pinfunction "2_2") (pintype "passive"))
      (node (ref "D15") (pin "2") (pinfunction "A_2") (pintype "passive"))
      (node (ref "D16") (pin "1") (pinfunction "C_1") (pintype "passive"))
    )
    (net (code "32") (name "Net-(D17-A)") (class "Default")
      (node (ref "Ci9") (pin "2") (pinfunction "2_2") (pintype "passive"))
      (node (ref "D17") (pin "2") (pinfunction "A_2") (pintype "passive"))
      (node (ref "D18") (pin "1") (pinfunction "C_1") (pintype "passive"))
    )
    (net (code "33") (name "Net-(D19-A)") (class "Default")
      (node (ref "Ci10") (pin "2") (pinfunction "2_2") (pintype "passive"))
      (node (ref "D19") (pin "2") (pinfunction "A_2") (pintype "passive"))
      (node (ref "D20") (pin "1") (pinfunction "C_1") (pintype "passive"))
    )
    (net (code "34") (name "Net-(D21-A)") (class "Default")
      (node (ref "Ci11") (pin "2") (pinfunction "2_2") (pintype "passive"))
      (node (ref "D21") (pin "2") (pinfunction "A_2") (pintype "passive"))
      (node (ref "D22") (pin "1") (pinfunction "C_1") (pintype "passive"))
    )
    (net (code "35") (name "Net-(D23-A)") (class "Default")
      (node (ref "Ci12") (pin "2") (pinfunction "2_2") (pintype "passive"))
      (node (ref "D23") (pin "2") (pinfunction "A_2") (pintype "passive"))
      (node (ref "D24") (pin "1") (pinfunction "C_1") (pintype "passive"))
    )
    (net (code "36") (name "Net-(D25-A)") (class "Default")
      (node (ref "Ci13") (pin "2") (pinfunction "2_2") (pintype "passive"))
      (node (ref "D25") (pin "2") (pinfunction "A_2") (pintype "passive"))
      (node (ref "D26") (pin "1") (pinfunction "C_1") (pintype "passive"))
    )
    (net (code "37") (name "Net-(D27-A)") (class "Default")
      (node (ref "Ci14") (pin "2") (pinfunction "2_2") (pintype "passive"))
      (node (ref "D27") (pin "2") (pinfunction "A_2") (pintype "passive"))
      (node (ref "D28") (pin "1") (pinfunction "C_1") (pintype "passive"))
    )
    (net (code "38") (name "Net-(D29-A)") (class "Default")
      (node (ref "Ci15") (pin "2") (pinfunction "2_2") (pintype "passive"))
      (node (ref "D29") (pin "2") (pinfunction "A_2") (pintype "passive"))
      (node (ref "D30") (pin "1") (pinfunction "C_1") (pintype "passive"))
    )
    (net (code "39") (name "Net-(D31-A)") (class "Default")
      (node (ref "Ci16") (pin "2") (pinfunction "2_2") (pintype "passive"))
      (node (ref "D31") (pin "2") (pinfunction "A_2") (pintype "passive"))
      (node (ref "D32") (pin "1") (pinfunction "C_1") (pintype "passive"))
    )
    (net (code "40") (name "Net-(D33-A)") (class "Default")
      (node (ref "Ci17") (pin "2") (pinfunction "2_2") (pintype "passive"))
      (node (ref "D33") (pin "2") (pinfunction "A_2") (pintype "passive"))
      (node (ref "D34") (pin "1") (pinfunction "C_1") (pintype "passive"))
    )
    (net (code "41") (name "Net-(D35-A)") (class "Default")
      (node (ref "Ci18") (pin "2") (pinfunction "2_2") (pintype "passive"))
      (node (ref "D35") (pin "2") (pinfunction "A_2") (pintype "passive"))
      (node (ref "D36") (pin "1") (pinfunction "C_1") (pintype "passive"))
    )
    (net (code "42") (name "Net-(D37-A)") (class "Default")
      (node (ref "Ci19") (pin "2") (pinfunction "2_2") (pintype "passive"))
      (node (ref "D37") (pin "2") (pinfunction "A_2") (pintype "passive"))
      (node (ref "D38") (pin "1") (pinfunction "C_1") (pintype "passive"))
    )
    (net (code "43") (name "Net-(D39-A)") (class "Default")
      (node (ref "Ci20") (pin "2") (pinfunction "2_2") (pintype "passive"))
      (node (ref "D39") (pin "2") (pinfunction "A_2") (pintype "passive"))
      (node (ref "D40") (pin "1") (pinfunction "C_1") (pintype "passive"))
    )
  )
)
